# Keyboard.net
KiCad netlist of a schematic drawn in EAGLE
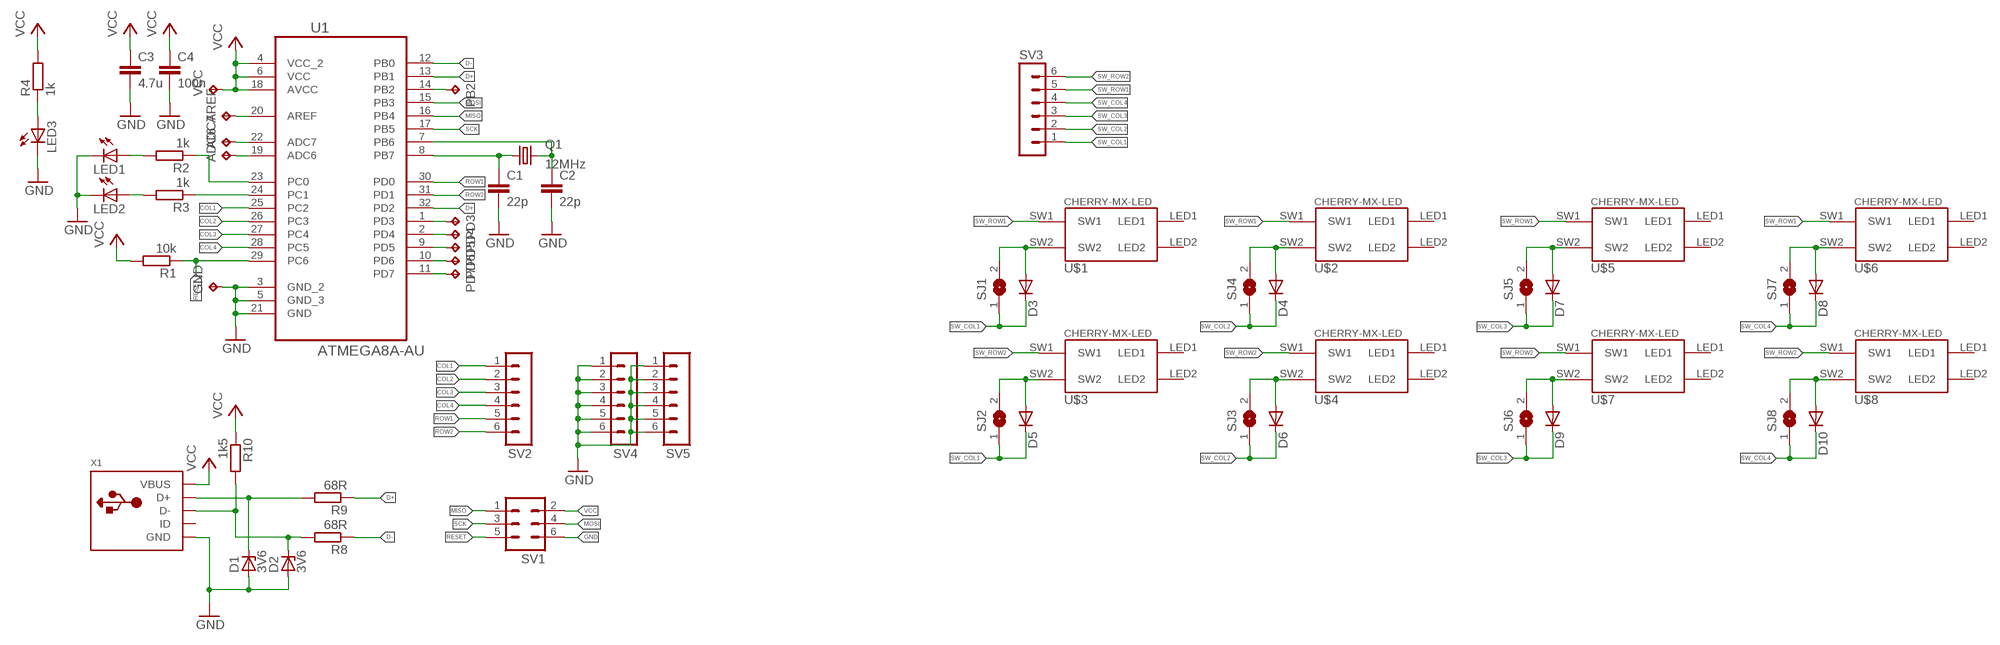
[diagram p0: schematic, sheet 1]

(export (version "E")
  (design (tool "Eeschema 10.0.6"))
  (components
    (comp (ref "ADC6")
      (value "TPB1,27")
      (footprint "eagle-import:B1,27")
      (libsource (lib "eagle-import") (part "TPB1,27"))
    )
    (comp (ref "ADC7")
      (value "TPB1,27")
      (footprint "eagle-import:B1,27")
      (libsource (lib "eagle-import") (part "TPB1,27"))
    )
    (comp (ref "AREF")
      (value "TPB1,27")
      (footprint "eagle-import:B1,27")
      (libsource (lib "eagle-import") (part "TPB1,27"))
    )
    (comp (ref "C1")
      (value "22p")
      (footprint "eagle-import:C0603")
      (libsource (lib "eagle-import") (part "C-EUC0603"))
    )
    (comp (ref "C2")
      (value "22p")
      (footprint "eagle-import:C0603")
      (libsource (lib "eagle-import") (part "C-EUC0603"))
    )
    (comp (ref "C3")
      (value "4.7u")
      (footprint "eagle-import:C0603")
      (libsource (lib "eagle-import") (part "C-EUC0603"))
    )
    (comp (ref "C4")
      (value "100n")
      (footprint "eagle-import:C0603")
      (libsource (lib "eagle-import") (part "C-EUC0603"))
    )
    (comp (ref "D1")
      (value "3V6")
      (footprint "eagle-import:SOD80C")
      (libsource (lib "eagle-import") (part "ZENER-DIODESOD80C"))
    )
    (comp (ref "D2")
      (value "3V6")
      (footprint "eagle-import:SOD80C")
      (libsource (lib "eagle-import") (part "ZENER-DIODESOD80C"))
    )
    (comp (ref "D3")
      (value "DIODE-MINIMELF")
      (footprint "eagle-import:MINIMELF")
      (libsource (lib "eagle-import") (part "DIODE-MINIMELF"))
    )
    (comp (ref "D4")
      (value "DIODE-MINIMELF")
      (footprint "eagle-import:MINIMELF")
      (libsource (lib "eagle-import") (part "DIODE-MINIMELF"))
    )
    (comp (ref "D5")
      (value "DIODE-MINIMELF")
      (footprint "eagle-import:MINIMELF")
      (libsource (lib "eagle-import") (part "DIODE-MINIMELF"))
    )
    (comp (ref "D6")
      (value "DIODE-MINIMELF")
      (footprint "eagle-import:MINIMELF")
      (libsource (lib "eagle-import") (part "DIODE-MINIMELF"))
    )
    (comp (ref "D7")
      (value "DIODE-MINIMELF")
      (footprint "eagle-import:MINIMELF")
      (libsource (lib "eagle-import") (part "DIODE-MINIMELF"))
    )
    (comp (ref "D8")
      (value "DIODE-MINIMELF")
      (footprint "eagle-import:MINIMELF")
      (libsource (lib "eagle-import") (part "DIODE-MINIMELF"))
    )
    (comp (ref "D9")
      (value "DIODE-MINIMELF")
      (footprint "eagle-import:MINIMELF")
      (libsource (lib "eagle-import") (part "DIODE-MINIMELF"))
    )
    (comp (ref "D10")
      (value "DIODE-MINIMELF")
      (footprint "eagle-import:MINIMELF")
      (libsource (lib "eagle-import") (part "DIODE-MINIMELF"))
    )
    (comp (ref "GND")
      (value "TPB1,27")
      (footprint "eagle-import:B1,27")
      (libsource (lib "eagle-import") (part "TPB1,27"))
    )
    (comp (ref "LED1")
      (value "LEDCHIP-LED0603")
      (footprint "eagle-import:CHIP-LED0603")
      (libsource (lib "eagle-import") (part "LEDCHIP-LED0603"))
    )
    (comp (ref "LED2")
      (value "LEDCHIP-LED0603")
      (footprint "eagle-import:CHIP-LED0603")
      (libsource (lib "eagle-import") (part "LEDCHIP-LED0603"))
    )
    (comp (ref "LED3")
      (value "LEDCHIP-LED0603")
      (footprint "eagle-import:CHIP-LED0603")
      (libsource (lib "eagle-import") (part "LEDCHIP-LED0603"))
    )
    (comp (ref "PB2")
      (value "TPB1,27")
      (footprint "eagle-import:B1,27")
      (libsource (lib "eagle-import") (part "TPB1,27"))
    )
    (comp (ref "PD3")
      (value "TPB1,27")
      (footprint "eagle-import:B1,27")
      (libsource (lib "eagle-import") (part "TPB1,27"))
    )
    (comp (ref "PD4")
      (value "TPB1,27")
      (footprint "eagle-import:B1,27")
      (libsource (lib "eagle-import") (part "TPB1,27"))
    )
    (comp (ref "PD5")
      (value "TPB1,27")
      (footprint "eagle-import:B1,27")
      (libsource (lib "eagle-import") (part "TPB1,27"))
    )
    (comp (ref "PD6")
      (value "TPB1,27")
      (footprint "eagle-import:B1,27")
      (libsource (lib "eagle-import") (part "TPB1,27"))
    )
    (comp (ref "PD7")
      (value "TPB1,27")
      (footprint "eagle-import:B1,27")
      (libsource (lib "eagle-import") (part "TPB1,27"))
    )
    (comp (ref "Q1")
      (value "12MHz")
      (footprint "eagle-import:11.4X4.5")
      (libsource (lib "eagle-import") (part "KX-K"))
    )
    (comp (ref "R1")
      (value "10k")
      (footprint "eagle-import:R0603")
      (libsource (lib "eagle-import") (part "R-EU_R0603"))
    )
    (comp (ref "R2")
      (value "1k")
      (footprint "eagle-import:R0603")
      (libsource (lib "eagle-import") (part "R-EU_R0603"))
    )
    (comp (ref "R3")
      (value "1k")
      (footprint "eagle-import:R0603")
      (libsource (lib "eagle-import") (part "R-EU_R0603"))
    )
    (comp (ref "R4")
      (value "1k")
      (footprint "eagle-import:R0603")
      (libsource (lib "eagle-import") (part "R-EU_R0603"))
    )
    (comp (ref "R8")
      (value "68R")
      (footprint "eagle-import:R0603")
      (libsource (lib "eagle-import") (part "R-EU_R0603"))
    )
    (comp (ref "R9")
      (value "68R")
      (footprint "eagle-import:R0603")
      (libsource (lib "eagle-import") (part "R-EU_R0603"))
    )
    (comp (ref "R10")
      (value "1k5")
      (footprint "eagle-import:R0603")
      (libsource (lib "eagle-import") (part "R-EU_R0603"))
    )
    (comp (ref "SJ1")
      (value "SJCLOSED")
      (footprint "eagle-import:SJC")
      (libsource (lib "eagle-import") (part "SJCLOSED"))
    )
    (comp (ref "SJ2")
      (value "SJCLOSED")
      (footprint "eagle-import:SJC")
      (libsource (lib "eagle-import") (part "SJCLOSED"))
    )
    (comp (ref "SJ3")
      (value "SJCLOSED")
      (footprint "eagle-import:SJC")
      (libsource (lib "eagle-import") (part "SJCLOSED"))
    )
    (comp (ref "SJ4")
      (value "SJCLOSED")
      (footprint "eagle-import:SJC")
      (libsource (lib "eagle-import") (part "SJCLOSED"))
    )
    (comp (ref "SJ5")
      (value "SJCLOSED")
      (footprint "eagle-import:SJC")
      (libsource (lib "eagle-import") (part "SJCLOSED"))
    )
    (comp (ref "SJ6")
      (value "SJCLOSED")
      (footprint "eagle-import:SJC")
      (libsource (lib "eagle-import") (part "SJCLOSED"))
    )
    (comp (ref "SJ7")
      (value "SJCLOSED")
      (footprint "eagle-import:SJC")
      (libsource (lib "eagle-import") (part "SJCLOSED"))
    )
    (comp (ref "SJ8")
      (value "SJCLOSED")
      (footprint "eagle-import:SJC")
      (libsource (lib "eagle-import") (part "SJCLOSED"))
    )
    (comp (ref "SV1")
      (value "MA03-2")
      (footprint "eagle-import:MA03-2")
      (libsource (lib "eagle-import") (part "MA03-2"))
    )
    (comp (ref "SV2")
      (value "MA06-1")
      (footprint "eagle-import:MA06-1")
      (libsource (lib "eagle-import") (part "MA06-1"))
    )
    (comp (ref "SV3")
      (value "MA06-1")
      (footprint "eagle-import:MA06-1")
      (libsource (lib "eagle-import") (part "MA06-1"))
    )
    (comp (ref "SV4")
      (value "MA06-1")
      (footprint "eagle-import:MA06-1")
      (libsource (lib "eagle-import") (part "MA06-1"))
    )
    (comp (ref "SV5")
      (value "MA06-1")
      (footprint "eagle-import:MA06-1")
      (libsource (lib "eagle-import") (part "MA06-1"))
    )
    (comp (ref "U$1")
      (value "CHERRY-MX-LED")
      (footprint "eagle-import:CHERRY-MX-LED")
      (libsource (lib "eagle-import") (part "CHERRY-MX-LED"))
    )
    (comp (ref "U$2")
      (value "CHERRY-MX-LED")
      (footprint "eagle-import:CHERRY-MX-LED")
      (libsource (lib "eagle-import") (part "CHERRY-MX-LED"))
    )
    (comp (ref "U$3")
      (value "CHERRY-MX-LED")
      (footprint "eagle-import:CHERRY-MX-LED")
      (libsource (lib "eagle-import") (part "CHERRY-MX-LED"))
    )
    (comp (ref "U$4")
      (value "CHERRY-MX-LED")
      (footprint "eagle-import:CHERRY-MX-LED")
      (libsource (lib "eagle-import") (part "CHERRY-MX-LED"))
    )
    (comp (ref "U$5")
      (value "CHERRY-MX-LED")
      (footprint "eagle-import:CHERRY-MX-LED")
      (libsource (lib "eagle-import") (part "CHERRY-MX-LED"))
    )
    (comp (ref "U$6")
      (value "CHERRY-MX-LED")
      (footprint "eagle-import:CHERRY-MX-LED")
      (libsource (lib "eagle-import") (part "CHERRY-MX-LED"))
    )
    (comp (ref "U$7")
      (value "CHERRY-MX-LED")
      (footprint "eagle-import:CHERRY-MX-LED")
      (libsource (lib "eagle-import") (part "CHERRY-MX-LED"))
    )
    (comp (ref "U$8")
      (value "CHERRY-MX-LED")
      (footprint "eagle-import:CHERRY-MX-LED")
      (libsource (lib "eagle-import") (part "CHERRY-MX-LED"))
    )
    (comp (ref "U1")
      (value "ATMEGA8A-AU")
      (footprint "eagle-import:QFP80P900X900X120-32N")
      (libsource (lib "eagle-import") (part "ATMEGA8A-AU"))
    )
    (comp (ref "VCC")
      (value "TPB1,27")
      (footprint "eagle-import:B1,27")
      (libsource (lib "eagle-import") (part "TPB1,27"))
    )
    (comp (ref "X1")
      (value "USB_MICRO_20329_V2")
      (footprint "eagle-import:4UCONN_20329_V2")
      (libsource (lib "eagle-import") (part "USB_MICRO_20329_V2"))
    )
  )
  (nets
    (net (code "1") (name "COL1") (class "Default")
      (node (ref "SV2") (pin "1") (pinfunction "1_1") (pintype "passive"))
      (node (ref "U1") (pin "25") (pinfunction "PC2_25") (pintype "bidirectional"))
    )
    (net (code "2") (name "COL2") (class "Default")
      (node (ref "SV2") (pin "2") (pinfunction "2_2") (pintype "passive"))
      (node (ref "U1") (pin "26") (pinfunction "PC3_26") (pintype "bidirectional"))
    )
    (net (code "3") (name "COL3") (class "Default")
      (node (ref "SV2") (pin "3") (pinfunction "3_3") (pintype "passive"))
      (node (ref "U1") (pin "27") (pinfunction "PC4_27") (pintype "bidirectional"))
    )
    (net (code "4") (name "COL4") (class "Default")
      (node (ref "SV2") (pin "4") (pinfunction "4_4") (pintype "passive"))
      (node (ref "U1") (pin "28") (pinfunction "PC5_28") (pintype "bidirectional"))
    )
    (net (code "5") (name "D+") (class "Default")
      (node (ref "R9") (pin "1") (pinfunction "1_1") (pintype "passive"))
      (node (ref "U1") (pin "13") (pinfunction "PB1_13") (pintype "passive"))
      (node (ref "U1") (pin "32") (pinfunction "PD2_32") (pintype "bidirectional"))
    )
    (net (code "6") (name "D-") (class "Default")
      (node (ref "R8") (pin "1") (pinfunction "1_1") (pintype "passive"))
      (node (ref "U1") (pin "12") (pinfunction "PB0_12") (pintype "passive"))
    )
    (net (code "7") (name "GND") (class "Default")
      (node (ref "C1") (pin "2") (pinfunction "2_2") (pintype "passive"))
      (node (ref "C2") (pin "2") (pinfunction "2_2") (pintype "passive"))
      (node (ref "C3") (pin "2") (pinfunction "2_2") (pintype "passive"))
      (node (ref "C4") (pin "2") (pinfunction "2_2") (pintype "passive"))
      (node (ref "D1") (pin "A") (pinfunction "A_A") (pintype "passive"))
      (node (ref "D2") (pin "A") (pinfunction "A_A") (pintype "passive"))
      (node (ref "GND") (pin "TP") (pinfunction "TP_TP") (pintype "input"))
      (node (ref "LED1") (pin "C") (pinfunction "C_C") (pintype "passive"))
      (node (ref "LED2") (pin "C") (pinfunction "C_C") (pintype "passive"))
      (node (ref "LED3") (pin "C") (pinfunction "C_C") (pintype "passive"))
      (node (ref "SV1") (pin "6") (pinfunction "6_6") (pintype "passive"))
      (node (ref "SV4") (pin "1") (pinfunction "1_1") (pintype "passive"))
      (node (ref "SV4") (pin "2") (pinfunction "2_2") (pintype "passive"))
      (node (ref "SV4") (pin "3") (pinfunction "3_3") (pintype "passive"))
      (node (ref "SV4") (pin "4") (pinfunction "4_4") (pintype "passive"))
      (node (ref "SV4") (pin "5") (pinfunction "5_5") (pintype "passive"))
      (node (ref "SV4") (pin "6") (pinfunction "6_6") (pintype "passive"))
      (node (ref "SV5") (pin "1") (pinfunction "1_1") (pintype "passive"))
      (node (ref "SV5") (pin "2") (pinfunction "2_2") (pintype "passive"))
      (node (ref "SV5") (pin "3") (pinfunction "3_3") (pintype "passive"))
      (node (ref "SV5") (pin "4") (pinfunction "4_4") (pintype "passive"))
      (node (ref "SV5") (pin "5") (pinfunction "5_5") (pintype "passive"))
      (node (ref "SV5") (pin "6") (pinfunction "6_6") (pintype "passive"))
      (node (ref "U1") (pin "21") (pinfunction "GND_21") (pintype "passive"))
      (node (ref "U1") (pin "3") (pinfunction "GND_2_3") (pintype "passive"))
      (node (ref "U1") (pin "5") (pinfunction "GND_3_5") (pintype "passive"))
      (node (ref "X1") (pin "BASE@1") (pinfunction "GND_BASE@1") (pintype "power_in"))
      (node (ref "X1") (pin "BASE@2") (pinfunction "GND_BASE@2") (pintype "power_in"))
      (node (ref "X1") (pin "GND") (pinfunction "GND_GND") (pintype "power_in"))
      (node (ref "X1") (pin "SPRT@1") (pinfunction "GND_SPRT@1") (pintype "power_in"))
      (node (ref "X1") (pin "SPRT@2") (pinfunction "GND_SPRT@2") (pintype "power_in"))
      (node (ref "X1") (pin "SPRT@3") (pinfunction "GND_SPRT@3") (pintype "power_in"))
      (node (ref "X1") (pin "SPRT@4") (pinfunction "GND_SPRT@4") (pintype "power_in"))
    )
    (net (code "8") (name "MISO") (class "Default")
      (node (ref "SV1") (pin "1") (pinfunction "1_1") (pintype "passive"))
      (node (ref "U1") (pin "16") (pinfunction "PB4_16") (pintype "passive"))
    )
    (net (code "9") (name "MOSI") (class "Default")
      (node (ref "SV1") (pin "4") (pinfunction "4_4") (pintype "passive"))
      (node (ref "U1") (pin "15") (pinfunction "PB3_15") (pintype "passive"))
    )
    (net (code "10") (name "Net-(D1-PadC)") (class "Default")
      (node (ref "D1") (pin "C") (pinfunction "C_C") (pintype "passive"))
      (node (ref "R9") (pin "2") (pinfunction "2_2") (pintype "passive"))
      (node (ref "X1") (pin "D+") (pinfunction "D+_D+") (pintype "bidirectional"))
    )
    (net (code "11") (name "Net-(D2-PadC)") (class "Default")
      (node (ref "D2") (pin "C") (pinfunction "C_C") (pintype "passive"))
      (node (ref "R10") (pin "2") (pinfunction "2_2") (pintype "passive"))
      (node (ref "R8") (pin "2") (pinfunction "2_2") (pintype "passive"))
      (node (ref "X1") (pin "D-") (pinfunction "D-_D-") (pintype "bidirectional"))
    )
    (net (code "12") (name "Net-(D3-PadA)") (class "Default")
      (node (ref "D3") (pin "A") (pinfunction "A_A") (pintype "passive"))
      (node (ref "SJ1") (pin "2") (pinfunction "2_2") (pintype "passive"))
      (node (ref "U$1") (pin "SW2") (pinfunction "SW2_SW2") (pintype "bidirectional"))
    )
    (net (code "13") (name "Net-(D4-PadA)") (class "Default")
      (node (ref "D4") (pin "A") (pinfunction "A_A") (pintype "passive"))
      (node (ref "SJ4") (pin "2") (pinfunction "2_2") (pintype "passive"))
      (node (ref "U$2") (pin "SW2") (pinfunction "SW2_SW2") (pintype "bidirectional"))
    )
    (net (code "14") (name "Net-(D5-PadA)") (class "Default")
      (node (ref "D5") (pin "A") (pinfunction "A_A") (pintype "passive"))
      (node (ref "SJ2") (pin "2") (pinfunction "2_2") (pintype "passive"))
      (node (ref "U$3") (pin "SW2") (pinfunction "SW2_SW2") (pintype "bidirectional"))
    )
    (net (code "15") (name "Net-(D6-PadA)") (class "Default")
      (node (ref "D6") (pin "A") (pinfunction "A_A") (pintype "passive"))
      (node (ref "SJ3") (pin "2") (pinfunction "2_2") (pintype "passive"))
      (node (ref "U$4") (pin "SW2") (pinfunction "SW2_SW2") (pintype "bidirectional"))
    )
    (net (code "16") (name "Net-(D7-PadA)") (class "Default")
      (node (ref "D7") (pin "A") (pinfunction "A_A") (pintype "passive"))
      (node (ref "SJ5") (pin "2") (pinfunction "2_2") (pintype "passive"))
      (node (ref "U$5") (pin "SW2") (pinfunction "SW2_SW2") (pintype "bidirectional"))
    )
    (net (code "17") (name "Net-(D8-PadA)") (class "Default")
      (node (ref "D8") (pin "A") (pinfunction "A_A") (pintype "passive"))
      (node (ref "SJ7") (pin "2") (pinfunction "2_2") (pintype "passive"))
      (node (ref "U$6") (pin "SW2") (pinfunction "SW2_SW2") (pintype "bidirectional"))
    )
    (net (code "18") (name "Net-(D9-PadA)") (class "Default")
      (node (ref "D9") (pin "A") (pinfunction "A_A") (pintype "passive"))
      (node (ref "SJ6") (pin "2") (pinfunction "2_2") (pintype "passive"))
      (node (ref "U$7") (pin "SW2") (pinfunction "SW2_SW2") (pintype "bidirectional"))
    )
    (net (code "19") (name "Net-(D10-PadA)") (class "Default")
      (node (ref "D10") (pin "A") (pinfunction "A_A") (pintype "passive"))
      (node (ref "SJ8") (pin "2") (pinfunction "2_2") (pintype "passive"))
      (node (ref "U$8") (pin "SW2") (pinfunction "SW2_SW2") (pintype "bidirectional"))
    )
    (net (code "20") (name "Net-(LED1-PadA)") (class "Default")
      (node (ref "LED1") (pin "A") (pinfunction "A_A") (pintype "passive"))
      (node (ref "R2") (pin "2") (pinfunction "2_2") (pintype "passive"))
    )
    (net (code "21") (name "Net-(LED2-PadA)") (class "Default")
      (node (ref "LED2") (pin "A") (pinfunction "A_A") (pintype "passive"))
      (node (ref "R3") (pin "2") (pinfunction "2_2") (pintype "passive"))
    )
    (net (code "22") (name "Net-(LED3-PadA)") (class "Default")
      (node (ref "LED3") (pin "A") (pinfunction "A_A") (pintype "passive"))
      (node (ref "R4") (pin "1") (pinfunction "1_1") (pintype "passive"))
    )
    (net (code "23") (name "Net-(U1-ADC6)") (class "Default")
      (node (ref "ADC6") (pin "TP") (pinfunction "TP_TP") (pintype "input"))
      (node (ref "U1") (pin "19") (pinfunction "ADC6_19") (pintype "input"))
    )
    (net (code "24") (name "Net-(U1-ADC7)") (class "Default")
      (node (ref "ADC7") (pin "TP") (pinfunction "TP_TP") (pintype "input"))
      (node (ref "U1") (pin "22") (pinfunction "ADC7_22") (pintype "input"))
    )
    (net (code "25") (name "Net-(U1-AREF)") (class "Default")
      (node (ref "AREF") (pin "TP") (pinfunction "TP_TP") (pintype "input"))
      (node (ref "U1") (pin "20") (pinfunction "AREF_20") (pintype "input"))
    )
    (net (code "26") (name "Net-(U1-PB2)") (class "Default")
      (node (ref "PB2") (pin "TP") (pinfunction "TP_TP") (pintype "input"))
      (node (ref "U1") (pin "14") (pinfunction "PB2_14") (pintype "passive"))
    )
    (net (code "27") (name "Net-(U1-PB6)") (class "Default")
      (node (ref "C2") (pin "1") (pinfunction "1_1") (pintype "passive"))
      (node (ref "Q1") (pin "2") (pinfunction "2_2") (pintype "passive"))
      (node (ref "U1") (pin "7") (pinfunction "PB6_7") (pintype "bidirectional"))
    )
    (net (code "28") (name "Net-(U1-PB7)") (class "Default")
      (node (ref "C1") (pin "1") (pinfunction "1_1") (pintype "passive"))
      (node (ref "Q1") (pin "1") (pinfunction "1_1") (pintype "passive"))
      (node (ref "U1") (pin "8") (pinfunction "PB7_8") (pintype "passive"))
    )
    (net (code "29") (name "Net-(U1-PC0)") (class "Default")
      (node (ref "R2") (pin "1") (pinfunction "1_1") (pintype "passive"))
      (node (ref "U1") (pin "23") (pinfunction "PC0_23") (pintype "bidirectional"))
    )
    (net (code "30") (name "Net-(U1-PC1)") (class "Default")
      (node (ref "R3") (pin "1") (pinfunction "1_1") (pintype "passive"))
      (node (ref "U1") (pin "24") (pinfunction "PC1_24") (pintype "bidirectional"))
    )
    (net (code "31") (name "Net-(U1-PD3)") (class "Default")
      (node (ref "PD3") (pin "TP") (pinfunction "TP_TP") (pintype "input"))
      (node (ref "U1") (pin "1") (pinfunction "PD3_1") (pintype "bidirectional"))
    )
    (net (code "32") (name "Net-(U1-PD4)") (class "Default")
      (node (ref "PD4") (pin "TP") (pinfunction "TP_TP") (pintype "input"))
      (node (ref "U1") (pin "2") (pinfunction "PD4_2") (pintype "bidirectional"))
    )
    (net (code "33") (name "Net-(U1-PD5)") (class "Default")
      (node (ref "PD5") (pin "TP") (pinfunction "TP_TP") (pintype "input"))
      (node (ref "U1") (pin "9") (pinfunction "PD5_9") (pintype "passive"))
    )
    (net (code "34") (name "Net-(U1-PD6)") (class "Default")
      (node (ref "PD6") (pin "TP") (pinfunction "TP_TP") (pintype "input"))
      (node (ref "U1") (pin "10") (pinfunction "PD6_10") (pintype "passive"))
    )
    (net (code "35") (name "Net-(U1-PD7)") (class "Default")
      (node (ref "PD7") (pin "TP") (pinfunction "TP_TP") (pintype "input"))
      (node (ref "U1") (pin "11") (pinfunction "PD7_11") (pintype "passive"))
    )
    (net (code "36") (name "RESET") (class "Default")
      (node (ref "R1") (pin "1") (pinfunction "1_1") (pintype "passive"))
      (node (ref "SV1") (pin "5") (pinfunction "5_5") (pintype "passive"))
      (node (ref "U1") (pin "29") (pinfunction "PC6_29") (pintype "bidirectional"))
    )
    (net (code "37") (name "ROW1") (class "Default")
      (node (ref "SV2") (pin "5") (pinfunction "5_5") (pintype "passive"))
      (node (ref "U1") (pin "30") (pinfunction "PD0_30") (pintype "bidirectional"))
    )
    (net (code "38") (name "ROW2") (class "Default")
      (node (ref "SV2") (pin "6") (pinfunction "6_6") (pintype "passive"))
      (node (ref "U1") (pin "31") (pinfunction "PD1_31") (pintype "bidirectional"))
    )
    (net (code "39") (name "SCK") (class "Default")
      (node (ref "SV1") (pin "3") (pinfunction "3_3") (pintype "passive"))
      (node (ref "U1") (pin "17") (pinfunction "PB5_17") (pintype "passive"))
    )
    (net (code "40") (name "SW_COL1") (class "Default")
      (node (ref "D3") (pin "C") (pinfunction "C_C") (pintype "passive"))
      (node (ref "D5") (pin "C") (pinfunction "C_C") (pintype "passive"))
      (node (ref "SJ1") (pin "1") (pinfunction "1_1") (pintype "passive"))
      (node (ref "SJ2") (pin "1") (pinfunction "1_1") (pintype "passive"))
      (node (ref "SV3") (pin "1") (pinfunction "1_1") (pintype "passive"))
    )
    (net (code "41") (name "SW_COL2") (class "Default")
      (node (ref "D4") (pin "C") (pinfunction "C_C") (pintype "passive"))
      (node (ref "D6") (pin "C") (pinfunction "C_C") (pintype "passive"))
      (node (ref "SJ3") (pin "1") (pinfunction "1_1") (pintype "passive"))
      (node (ref "SJ4") (pin "1") (pinfunction "1_1") (pintype "passive"))
      (node (ref "SV3") (pin "2") (pinfunction "2_2") (pintype "passive"))
    )
    (net (code "42") (name "SW_COL3") (class "Default")
      (node (ref "D7") (pin "C") (pinfunction "C_C") (pintype "passive"))
      (node (ref "D9") (pin "C") (pinfunction "C_C") (pintype "passive"))
      (node (ref "SJ5") (pin "1") (pinfunction "1_1") (pintype "passive"))
      (node (ref "SJ6") (pin "1") (pinfunction "1_1") (pintype "passive"))
      (node (ref "SV3") (pin "3") (pinfunction "3_3") (pintype "passive"))
    )
    (net (code "43") (name "SW_COL4") (class "Default")
      (node (ref "D10") (pin "C") (pinfunction "C_C") (pintype "passive"))
      (node (ref "D8") (pin "C") (pinfunction "C_C") (pintype "passive"))
      (node (ref "SJ7") (pin "1") (pinfunction "1_1") (pintype "passive"))
      (node (ref "SJ8") (pin "1") (pinfunction "1_1") (pintype "passive"))
      (node (ref "SV3") (pin "4") (pinfunction "4_4") (pintype "passive"))
    )
    (net (code "44") (name "SW_ROW1") (class "Default")
      (node (ref "SV3") (pin "5") (pinfunction "5_5") (pintype "passive"))
      (node (ref "U$1") (pin "SW1") (pinfunction "SW1_SW1") (pintype "bidirectional"))
      (node (ref "U$2") (pin "SW1") (pinfunction "SW1_SW1") (pintype "bidirectional"))
      (node (ref "U$5") (pin "SW1") (pinfunction "SW1_SW1") (pintype "bidirectional"))
      (node (ref "U$6") (pin "SW1") (pinfunction "SW1_SW1") (pintype "bidirectional"))
    )
    (net (code "45") (name "SW_ROW2") (class "Default")
      (node (ref "SV3") (pin "6") (pinfunction "6_6") (pintype "passive"))
      (node (ref "U$3") (pin "SW1") (pinfunction "SW1_SW1") (pintype "bidirectional"))
      (node (ref "U$4") (pin "SW1") (pinfunction "SW1_SW1") (pintype "bidirectional"))
      (node (ref "U$7") (pin "SW1") (pinfunction "SW1_SW1") (pintype "bidirectional"))
      (node (ref "U$8") (pin "SW1") (pinfunction "SW1_SW1") (pintype "bidirectional"))
    )
    (net (code "46") (name "VCC") (class "Default")
      (node (ref "C3") (pin "1") (pinfunction "1_1") (pintype "passive"))
      (node (ref "C4") (pin "1") (pinfunction "1_1") (pintype "passive"))
      (node (ref "R1") (pin "2") (pinfunction "2_2") (pintype "passive"))
      (node (ref "R10") (pin "1") (pinfunction "1_1") (pintype "passive"))
      (node (ref "R4") (pin "2") (pinfunction "2_2") (pintype "passive"))
      (node (ref "SV1") (pin "2") (pinfunction "2_2") (pintype "passive"))
      (node (ref "U1") (pin "18") (pinfunction "AVCC_18") (pintype "power_in"))
      (node (ref "U1") (pin "4") (pinfunction "VCC_2_4") (pintype "power_in"))
      (node (ref "U1") (pin "6") (pinfunction "VCC_6") (pintype "power_in"))
      (node (ref "VCC") (pin "TP") (pinfunction "TP_TP") (pintype "input"))
      (node (ref "X1") (pin "VBUS") (pinfunction "VBUS_VBUS") (pintype "power_in"))
    )
    (net (code "47") (name "unconnected-(U$1-PadLED1)") (class "Default")
      (node (ref "U$1") (pin "LED1") (pinfunction "LED1_LED1") (pintype "bidirectional"))
    )
    (net (code "48") (name "unconnected-(U$1-PadLED2)") (class "Default")
      (node (ref "U$1") (pin "LED2") (pinfunction "LED2_LED2") (pintype "bidirectional"))
    )
    (net (code "49") (name "unconnected-(U$2-PadLED1)") (class "Default")
      (node (ref "U$2") (pin "LED1") (pinfunction "LED1_LED1") (pintype "bidirectional"))
    )
    (net (code "50") (name "unconnected-(U$2-PadLED2)") (class "Default")
      (node (ref "U$2") (pin "LED2") (pinfunction "LED2_LED2") (pintype "bidirectional"))
    )
    (net (code "51") (name "unconnected-(U$3-PadLED1)") (class "Default")
      (node (ref "U$3") (pin "LED1") (pinfunction "LED1_LED1") (pintype "bidirectional"))
    )
    (net (code "52") (name "unconnected-(U$3-PadLED2)") (class "Default")
      (node (ref "U$3") (pin "LED2") (pinfunction "LED2_LED2") (pintype "bidirectional"))
    )
    (net (code "53") (name "unconnected-(U$4-PadLED1)") (class "Default")
      (node (ref "U$4") (pin "LED1") (pinfunction "LED1_LED1") (pintype "bidirectional"))
    )
    (net (code "54") (name "unconnected-(U$4-PadLED2)") (class "Default")
      (node (ref "U$4") (pin "LED2") (pinfunction "LED2_LED2") (pintype "bidirectional"))
    )
    (net (code "55") (name "unconnected-(U$5-PadLED1)") (class "Default")
      (node (ref "U$5") (pin "LED1") (pinfunction "LED1_LED1") (pintype "bidirectional"))
    )
    (net (code "56") (name "unconnected-(U$5-PadLED2)") (class "Default")
      (node (ref "U$5") (pin "LED2") (pinfunction "LED2_LED2") (pintype "bidirectional"))
    )
    (net (code "57") (name "unconnected-(U$6-PadLED1)") (class "Default")
      (node (ref "U$6") (pin "LED1") (pinfunction "LED1_LED1") (pintype "bidirectional"))
    )
    (net (code "58") (name "unconnected-(U$6-PadLED2)") (class "Default")
      (node (ref "U$6") (pin "LED2") (pinfunction "LED2_LED2") (pintype "bidirectional"))
    )
    (net (code "59") (name "unconnected-(U$7-PadLED1)") (class "Default")
      (node (ref "U$7") (pin "LED1") (pinfunction "LED1_LED1") (pintype "bidirectional"))
    )
    (net (code "60") (name "unconnected-(U$7-PadLED2)") (class "Default")
      (node (ref "U$7") (pin "LED2") (pinfunction "LED2_LED2") (pintype "bidirectional"))
    )
    (net (code "61") (name "unconnected-(U$8-PadLED1)") (class "Default")
      (node (ref "U$8") (pin "LED1") (pinfunction "LED1_LED1") (pintype "bidirectional"))
    )
    (net (code "62") (name "unconnected-(U$8-PadLED2)") (class "Default")
      (node (ref "U$8") (pin "LED2") (pinfunction "LED2_LED2") (pintype "bidirectional"))
    )
    (net (code "63") (name "unconnected-(X1-PadID)") (class "Default")
      (node (ref "X1") (pin "ID") (pinfunction "ID_ID") (pintype "bidirectional"))
    )
  )
)
